# breakout_mcp9804.net
KiCad netlist of a schematic drawn in EAGLE
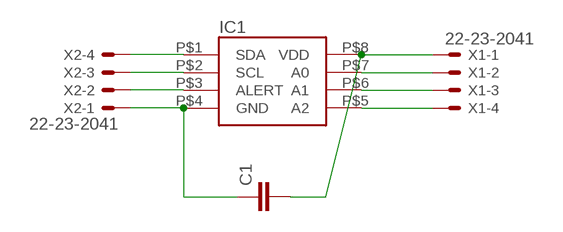
[diagram p0: schematic, sheet 1]

(export (version "E")
  (design (tool "Eeschema 10.0.6"))
  (components
    (comp (ref "C1")
      (value "C-EUC1206")
      (footprint "eagle-import:C1206")
      (libsource (lib "eagle-import") (part "C-EUC1206"))
    )
    (comp (ref "IC1")
      (value "MPC9804")
      (footprint "eagle-import:MSOP-8")
      (libsource (lib "eagle-import") (part "MPC9804"))
    )
    (comp (ref "X1")
      (value "22-23-2041")
      (footprint "eagle-import:22-23-2041")
      (fields (field (name "MF") "MOLEX"))
      (libsource (lib "eagle-import") (part "22-23-2041"))
    )
    (comp (ref "X2")
      (value "22-23-2041")
      (footprint "eagle-import:22-23-2041")
      (fields (field (name "MF") "MOLEX"))
      (libsource (lib "eagle-import") (part "22-23-2041"))
    )
  )
  (nets
    (net (code "1") (name "Net-(IC1-A0)") (class "Default")
      (node (ref "IC1") (pin "P$7") (pinfunction "A0_P$7") (pintype "input"))
      (node (ref "X1") (pin "2") (pinfunction "S_2") (pintype "passive"))
    )
    (net (code "2") (name "Net-(IC1-A1)") (class "Default")
      (node (ref "IC1") (pin "P$6") (pinfunction "A1_P$6") (pintype "input"))
      (node (ref "X1") (pin "3") (pinfunction "S_3") (pintype "passive"))
    )
    (net (code "3") (name "Net-(IC1-A2)") (class "Default")
      (node (ref "IC1") (pin "P$5") (pinfunction "A2_P$5") (pintype "input"))
      (node (ref "X1") (pin "4") (pinfunction "S_4") (pintype "passive"))
    )
    (net (code "4") (name "Net-(IC1-ALERT)") (class "Default")
      (node (ref "IC1") (pin "P$3") (pinfunction "ALERT_P$3") (pintype "output"))
      (node (ref "X2") (pin "2") (pinfunction "S_2") (pintype "passive"))
    )
    (net (code "5") (name "Net-(IC1-GND)") (class "Default")
      (node (ref "C1") (pin "1") (pinfunction "1_1") (pintype "passive"))
      (node (ref "IC1") (pin "P$4") (pinfunction "GND_P$4") (pintype "power_in"))
      (node (ref "X2") (pin "1") (pinfunction "S_1") (pintype "passive"))
    )
    (net (code "6") (name "Net-(IC1-SCL)") (class "Default")
      (node (ref "IC1") (pin "P$2") (pinfunction "SCL_P$2") (pintype "output"))
      (node (ref "X2") (pin "3") (pinfunction "S_3") (pintype "passive"))
    )
    (net (code "7") (name "Net-(IC1-SDA)") (class "Default")
      (node (ref "IC1") (pin "P$1") (pinfunction "SDA_P$1") (pintype "bidirectional"))
      (node (ref "X2") (pin "4") (pinfunction "S_4") (pintype "passive"))
    )
    (net (code "8") (name "Net-(IC1-VDD)") (class "Default")
      (node (ref "C1") (pin "2") (pinfunction "2_2") (pintype "passive"))
      (node (ref "IC1") (pin "P$8") (pinfunction "VDD_P$8") (pintype "power_in"))
      (node (ref "X1") (pin "1") (pinfunction "S_1") (pintype "passive"))
    )
  )
)
